# CH32V103C-R1.net
KiCad netlist of a schematic drawn in Altium Designer
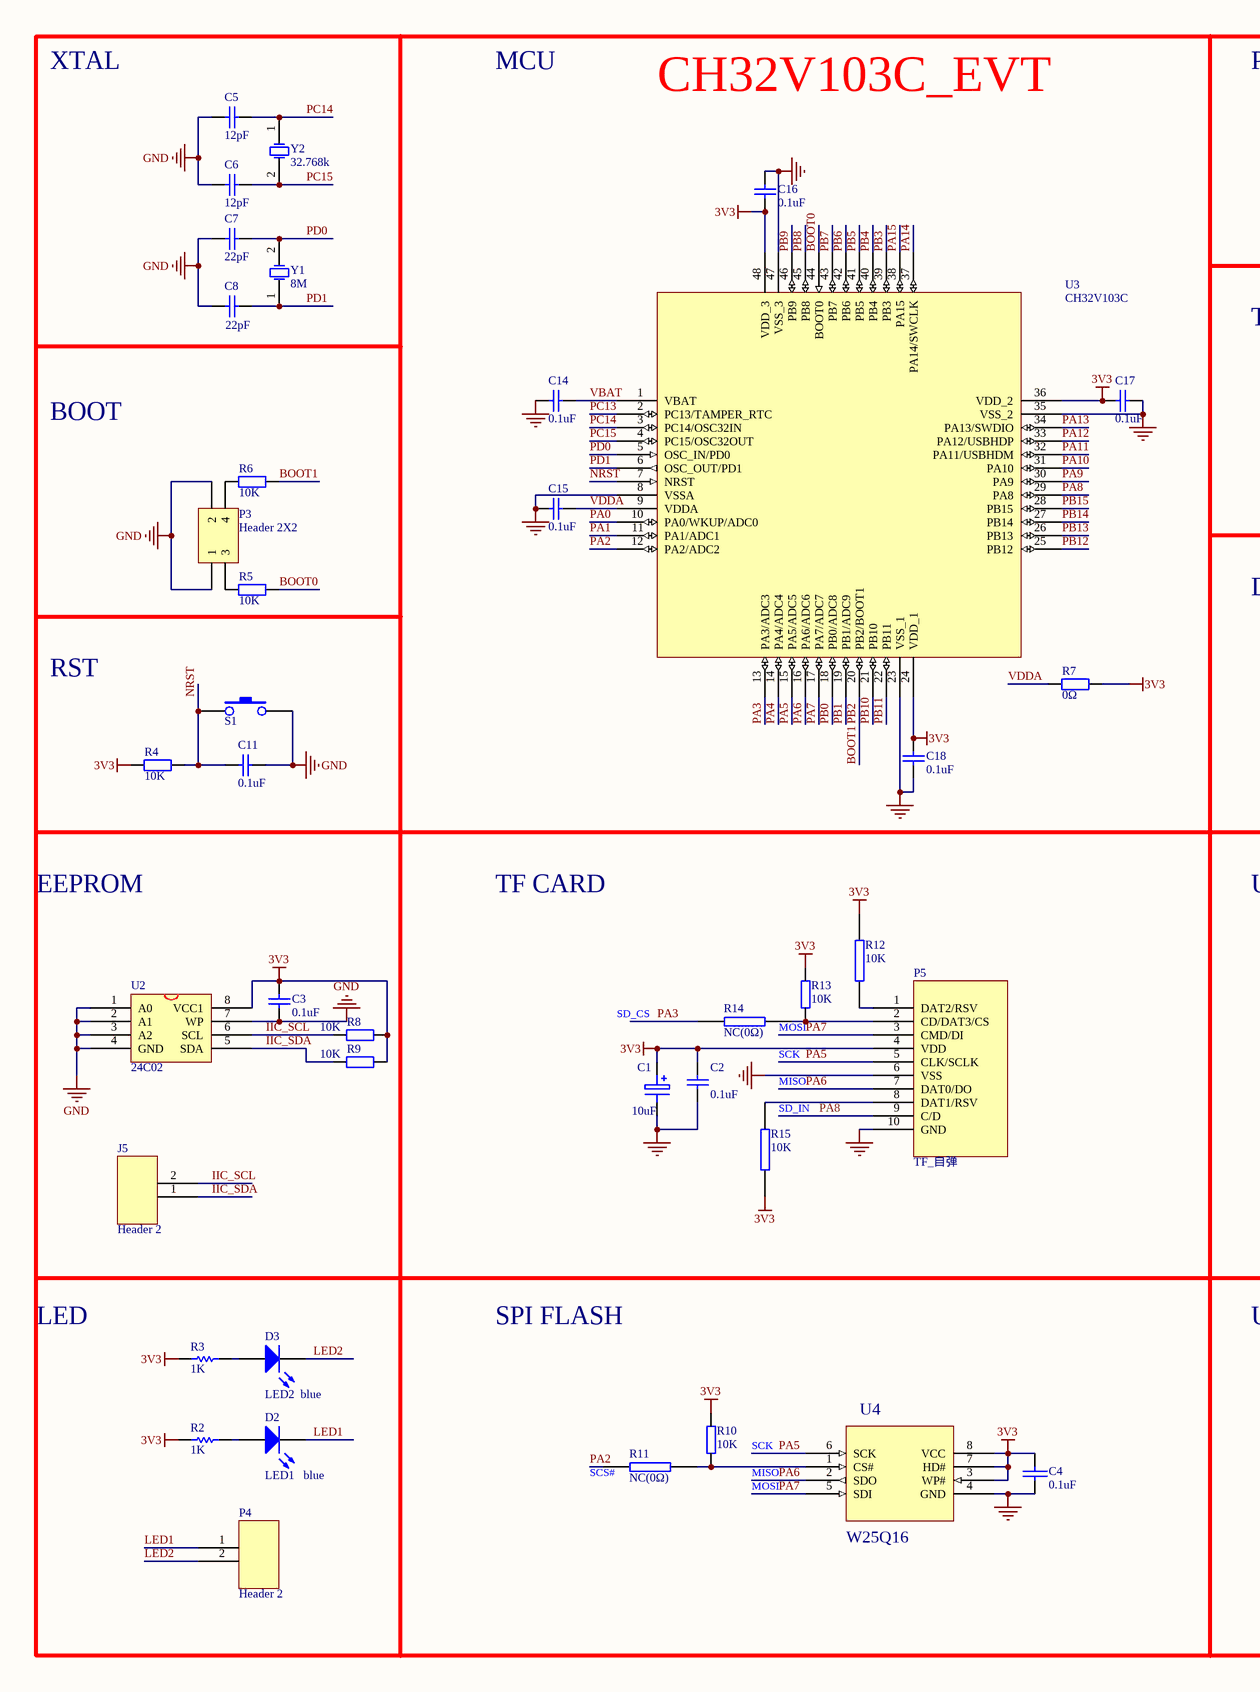
[diagram p0: CH32V103C-R1.SchDoc, left]
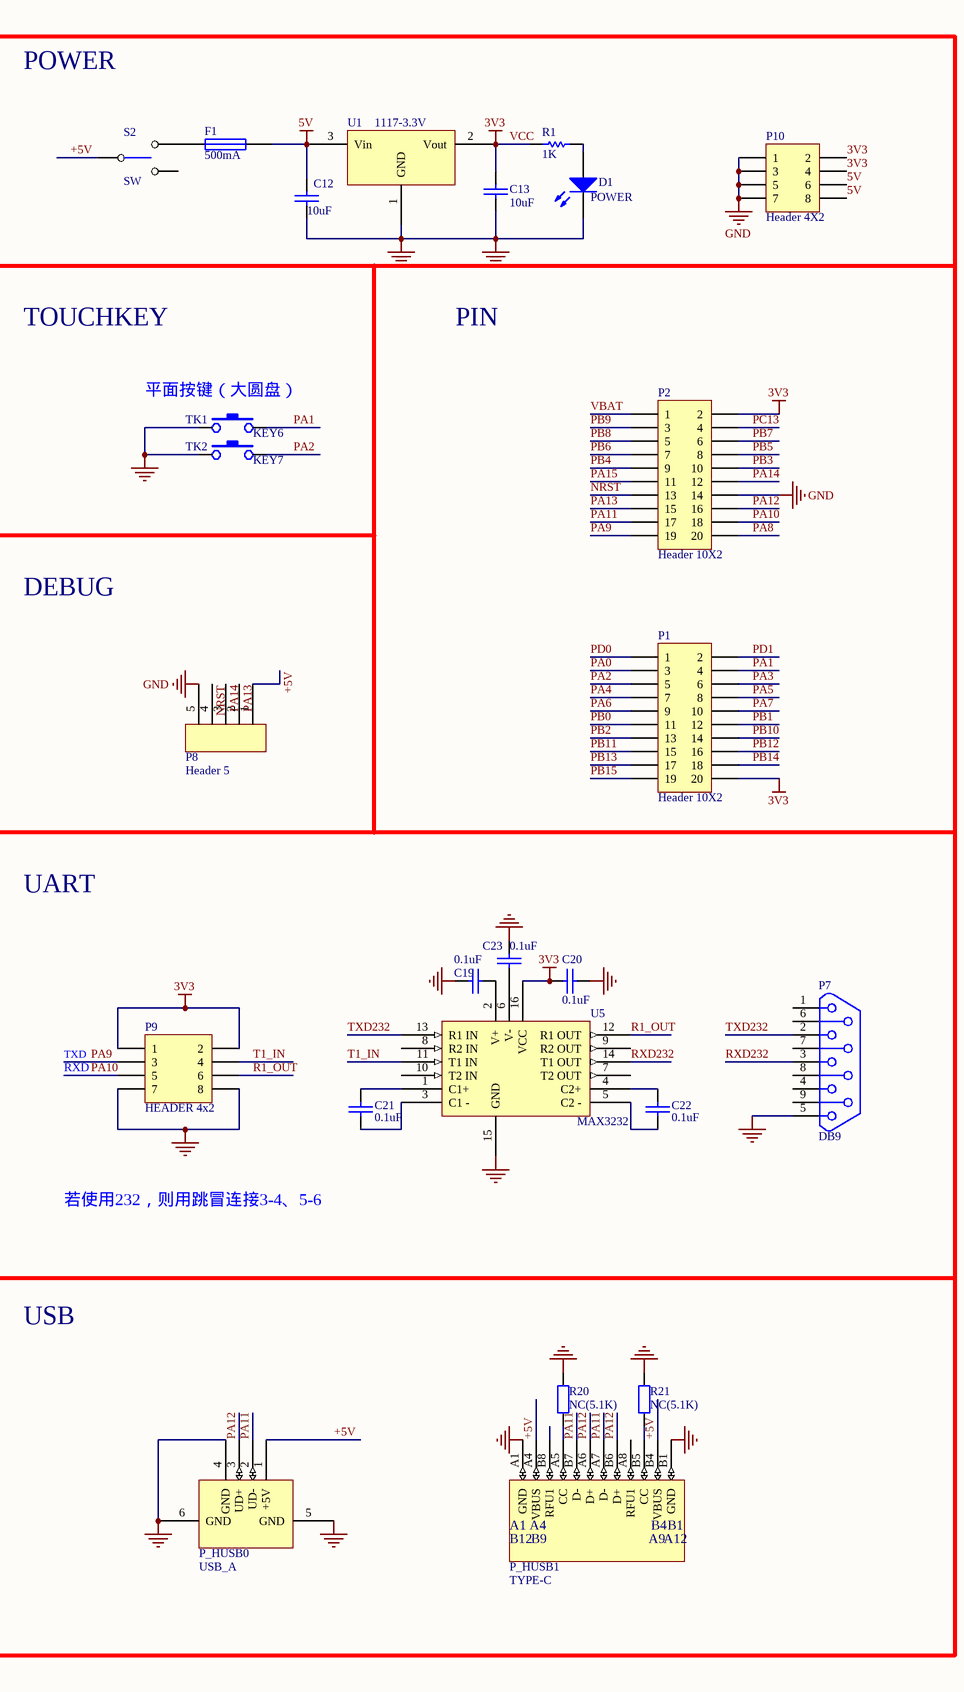
[diagram p1: CH32V103C-R1.SchDoc, right]

(export (version "E")
  (design (tool "Eeschema 10.0.6"))
  (components
    (comp (ref "C1")
      (value "10uF")
      (footprint "3216")
      (description "Electrolytic Capacitor")
      (libsource (lib "*") (part "ELECTRO1"))
    )
    (comp (ref "C2")
      (value "0.1uF")
      (footprint "0603")
      (description "Capacitor")
      (fields (field (name "PUBLISHER") "Altium Limited"))
      (libsource (lib "*") (part "Cap"))
    )
    (comp (ref "C3")
      (value "0.1uF")
      (footprint "0603")
      (description "Capacitor")
      (fields (field (name "PUBLISHER") "Altium Limited"))
      (libsource (lib "Miscellaneous Devices") (part "Cap"))
    )
    (comp (ref "C4")
      (value "0.1uF")
      (footprint "0603")
      (description "Capacitor")
      (libsource (lib "*") (part "CAP"))
    )
    (comp (ref "C5")
      (value "12pF")
      (footprint "0603")
      (description "Capacitor")
      (fields (field (name "PUBLISHER") "Altium Limited"))
      (libsource (lib "Miscellaneous Devices") (part "Cap"))
    )
    (comp (ref "C6")
      (value "12pF")
      (footprint "0603")
      (description "Capacitor")
      (fields (field (name "PUBLISHER") "Altium Limited"))
      (libsource (lib "Miscellaneous Devices") (part "Cap"))
    )
    (comp (ref "C7")
      (value "22pF")
      (footprint "0603")
      (description "Capacitor")
      (fields (field (name "PUBLISHER") "Altium Limited"))
      (libsource (lib "Miscellaneous Devices") (part "Cap"))
    )
    (comp (ref "C8")
      (value "22pF")
      (footprint "0603")
      (description "Capacitor")
      (fields (field (name "PUBLISHER") "Altium Limited"))
      (libsource (lib "Miscellaneous Devices") (part "Cap"))
    )
    (comp (ref "C11")
      (value "0.1uF")
      (footprint "0603")
      (description "Capacitor")
      (fields (field (name "PUBLISHER") "Altium Limited"))
      (libsource (lib "Miscellaneous Devices") (part "Cap"))
    )
    (comp (ref "C12")
      (value "10uF")
      (footprint "3216")
      (description "Capacitor")
      (libsource (lib "") (part "CAP_1"))
    )
    (comp (ref "C13")
      (value "10uF")
      (footprint "0603")
      (description "Capacitor")
      (libsource (lib "") (part "CAP_1"))
    )
    (comp (ref "C14")
      (value "0.1uF")
      (footprint "0603")
      (description "Capacitor")
      (fields (field (name "PUBLISHER") "Altium Limited"))
      (libsource (lib "*") (part "Cap"))
    )
    (comp (ref "C15")
      (value "0.1uF")
      (footprint "0603")
      (description "Capacitor")
      (fields (field (name "PUBLISHER") "Altium Limited"))
      (libsource (lib "*") (part "Cap"))
    )
    (comp (ref "C16")
      (value "0.1uF")
      (footprint "0603")
      (description "Capacitor")
      (fields (field (name "PUBLISHER") "Altium Limited"))
      (libsource (lib "*") (part "Cap"))
    )
    (comp (ref "C17")
      (value "0.1uF")
      (footprint "0603")
      (description "Capacitor")
      (fields (field (name "PUBLISHER") "Altium Limited"))
      (libsource (lib "*") (part "Cap"))
    )
    (comp (ref "C18")
      (value "0.1uF")
      (footprint "0603")
      (description "Capacitor")
      (fields (field (name "PUBLISHER") "Altium Limited"))
      (libsource (lib "*") (part "Cap"))
    )
    (comp (ref "C19")
      (value "0.1uF")
      (footprint "0603")
      (description "Capacitor")
      (libsource (lib "*") (part "CAP"))
    )
    (comp (ref "C20")
      (value "0.1uF")
      (footprint "0603")
      (description "Capacitor")
      (libsource (lib "*") (part "CAP"))
    )
    (comp (ref "C21")
      (value "0.1uF")
      (footprint "0603")
      (description "Capacitor")
      (libsource (lib "*") (part "CAP"))
    )
    (comp (ref "C22")
      (value "0.1uF")
      (footprint "0603")
      (description "Capacitor")
      (libsource (lib "*") (part "CAP"))
    )
    (comp (ref "C23")
      (value "0.1uF")
      (footprint "0603")
      (description "Capacitor")
      (libsource (lib "*") (part "CAP"))
    )
    (comp (ref "D1")
      (value "POWER")
      (footprint "0603+")
      (description "Typical INFRARED GaAs LED")
      (fields (field (name "PUBLISHER") "Altium Limited"))
      (libsource (lib "Miscellaneous Devices") (part "LED0"))
    )
    (comp (ref "D2")
      (value "LED1   blue")
      (footprint "0603+")
      (description "Typical INFRARED GaAs LED")
      (fields (field (name "PUBLISHER") "Altium Limited"))
      (libsource (lib "Miscellaneous Devices") (part "LED0"))
    )
    (comp (ref "D3")
      (value "LED2  blue")
      (footprint "0603+")
      (description "Typical INFRARED GaAs LED")
      (fields (field (name "PUBLISHER") "Altium Limited"))
      (libsource (lib "Miscellaneous Devices") (part "LED0"))
    )
    (comp (ref "F1")
      (value "500mA")
      (footprint "0603")
      (description "Fuse")
      (libsource (lib "*") (part "FUSE1"))
    )
    (comp (ref "J5") (value "Header 2") (footprint "SIP2-2.54mm") (libsource (lib "MYSCH") (part "2HEAD")))
    (comp (ref "P1")
      (value "Header 10X2")
      (footprint "IDC20-2.54mm")
      (description "Header, 10-Pin, Dual row")
      (fields (field (name "PUBLISHER") "Altium Limited"))
      (libsource (lib "Miscellaneous Connectors") (part "Header 10X2"))
    )
    (comp (ref "P2")
      (value "Header 10X2")
      (footprint "IDC20-2.54mm")
      (description "Header, 10-Pin, Dual row")
      (fields (field (name "PUBLISHER") "Altium Limited"))
      (libsource (lib "Miscellaneous Connectors") (part "Header 10X2"))
    )
    (comp (ref "P3")
      (value "Header 2X2")
      (footprint "HDR2X2")
      (description "Header, 2-Pin, Dual row")
      (fields (field (name "PUBLISHER") "Altium Limited"))
      (libsource (lib "Miscellaneous Connectors") (part "Header 2X2"))
    )
    (comp (ref "P4") (value "Header 2") (footprint "SIP2-2.54mm") (libsource (lib "") (part "2HEAD_1")))
    (comp (ref "P5") (value "TF_自弹") (footprint "TF") (libsource (lib "*") (part "TF_自弹")))
    (comp (ref "P7") (value "DB9") (footprint "DB9/M") (libsource (lib "*") (part "DB9")))
    (comp (ref "P8")
      (value "Header 5")
      (footprint "SIP5-2.54mm")
      (libsource (lib "PCB_Project1") (part "2HEAD"))
    )
    (comp (ref "P9")
      (value "HEADER 4x2")
      (footprint "MYPCB:IDC8-2.54mm")
      (description "Header, 4-Pin, Dual row")
      (libsource (lib "wch_sch_others") (part "HEADER 4x2"))
    )
    (comp (ref "P10")
      (value "Header 4X2")
      (footprint "IDC8-2.54mm")
      (description "Header, 4-Pin, Dual row")
      (fields (field (name "PUBLISHER") "Altium Limited"))
      (libsource (lib "Miscellaneous Connectors") (part "Header 4X2"))
    )
    (comp (ref "P_HUSB0")
      (value "USB_A")
      (footprint "USBA-l")
      (description "USB Port")
      (libsource (lib "CHXXXSCH") (part "USB"))
    )
    (comp (ref "P_HUSB1")
      (value "TYPE-C")
      (footprint "TYPE-C-Receptacle-2.0")
      (libsource (lib "*") (part "TYPE-C1"))
    )
    (comp (ref "R1")
      (value "1K")
      (footprint "0603")
      (description "Semiconductor Resistor")
      (fields (field (name "PUBLISHER") "Altium Limited"))
      (libsource (lib "Miscellaneous Devices") (part "Res Semi"))
    )
    (comp (ref "R2")
      (value "1K")
      (footprint "0603")
      (description "Semiconductor Resistor")
      (fields (field (name "PUBLISHER") "Altium Limited"))
      (libsource (lib "Miscellaneous Devices") (part "Res Semi"))
    )
    (comp (ref "R3")
      (value "1K")
      (footprint "0603")
      (description "Semiconductor Resistor")
      (fields (field (name "PUBLISHER") "Altium Limited"))
      (libsource (lib "Miscellaneous Devices") (part "Res Semi"))
    )
    (comp (ref "R4")
      (value "10K")
      (footprint "0603")
      (description "Resistor")
      (fields (field (name "PUBLISHER") "Altium Limited"))
      (libsource (lib "Miscellaneous Devices") (part "Res2"))
    )
    (comp (ref "R5")
      (value "10K")
      (footprint "0603")
      (description "Resistor")
      (fields (field (name "PUBLISHER") "Altium Limited"))
      (libsource (lib "Miscellaneous Devices") (part "Res2"))
    )
    (comp (ref "R6")
      (value "10K")
      (footprint "0603")
      (description "Resistor")
      (fields (field (name "PUBLISHER") "Altium Limited"))
      (libsource (lib "Miscellaneous Devices") (part "Res2"))
    )
    (comp (ref "R7")
      (value "0Ω")
      (footprint "0603")
      (description "Resistor")
      (fields (field (name "PUBLISHER") "Altium Limited"))
      (libsource (lib "Miscellaneous Devices") (part "Res2"))
    )
    (comp (ref "R8")
      (value "10K")
      (footprint "0603")
      (description "Resistor")
      (fields (field (name "PUBLISHER") "Altium Limited"))
      (libsource (lib "Miscellaneous Devices") (part "Res2"))
    )
    (comp (ref "R9")
      (value "10K")
      (footprint "0603")
      (description "Resistor")
      (fields (field (name "PUBLISHER") "Altium Limited"))
      (libsource (lib "Miscellaneous Devices") (part "Res2"))
    )
    (comp (ref "R10") (value "10K") (footprint "0603") (libsource (lib "*") (part "DZ")))
    (comp (ref "R11") (value "NC(0Ω)") (footprint "0603") (libsource (lib "*") (part "RES2")))
    (comp (ref "R12") (value "10K") (footprint "0603") (libsource (lib "*") (part "RES2")))
    (comp (ref "R13") (value "10K") (footprint "0603") (libsource (lib "*") (part "DZ")))
    (comp (ref "R14") (value "NC(0Ω)") (footprint "0603") (libsource (lib "*") (part "RES2")))
    (comp (ref "R15") (value "10K") (footprint "0603") (libsource (lib "*") (part "RES2")))
    (comp (ref "R20")
      (value "NC(5.1K)")
      (footprint "0603")
      (description "Resistor")
      (libsource (lib "") (part "Res2_1"))
    )
    (comp (ref "R21")
      (value "NC(5.1K)")
      (footprint "0603")
      (description "Resistor")
      (libsource (lib "") (part "Res2_1"))
    )
    (comp (ref "S1") (value "KEY") (footprint "贴片按键") (libsource (lib "CCDXPLIB") (part "KEY")))
    (comp (ref "S2") (value "SW") (footprint "KEY2") (libsource (lib "MYSCH") (part "SW")))
    (comp (ref "TK1") (value "KEY6") (footprint "TOUCHKEY-12mm") (libsource (lib "*") (part "KEY")))
    (comp (ref "TK2") (value "KEY7") (footprint "TOUCHKEY-12mm") (libsource (lib "*") (part "KEY")))
    (comp (ref "U1")
      (value "1117-3.3V")
      (footprint "SOT-223")
      (libsource (lib "wch_sch_others") (part "1117-3.3V"))
    )
    (comp (ref "U2") (value "24C02") (footprint "SOP8") (libsource (lib "Elite_SCH") (part "24C256")))
    (comp (ref "U3")
      (value "CH32V103C")
      (footprint "LQFP48")
      (description "RISC-V MCU with USB device & USB host & ADC & Touch Key")
      (libsource (lib "CHXXX") (part "CH32V103C"))
    )
    (comp (ref "U4")
      (value "W25Q16")
      (footprint "SOIC-8_208mil")
      (libsource (lib "*") (part "Pro89C.tmp_25F512_2"))
    )
    (comp (ref "U5")
      (value "MAX3232")
      (footprint "SOIC-16_150mil")
      (description "+-15KV ESD-PROTECTED, +5V RS-232 TRANSCEIVERS")
      (libsource (lib "*") (part "MAX232CPE(16)"))
    )
    (comp (ref "Y1")
      (value "8M")
      (footprint "XT62/28")
      (description "Crystal Oscillator")
      (fields (field (name "PUBLISHER") "Altium Limited"))
      (libsource (lib "Miscellaneous Devices") (part "XTAL"))
    )
    (comp (ref "Y2")
      (value "32.768k")
      (footprint "FC-135")
      (description "Crystal Oscillator")
      (fields (field (name "PUBLISHER") "Altium Limited"))
      (libsource (lib "Miscellaneous Devices") (part "XTAL"))
    )
  )
  (nets
    (net (code "1") (name "/+5V") (class "Default")
      (node (ref "P8") (pin "1") (pintype "passive"))
      (node (ref "P_HUSB0") (pin "1") (pinfunction "+5V_1") (pintype "power_in"))
      (node (ref "P_HUSB1") (pin "A4") (pinfunction "VBUS_A4") (pintype "bidirectional"))
      (node (ref "P_HUSB1") (pin "B4") (pinfunction "VBUS_B4") (pintype "bidirectional"))
      (node (ref "S2") (pin "1") (pinfunction "1_1") (pintype "passive"))
    )
    (net (code "3") (name "/BOOT0") (class "Default")
      (node (ref "R5") (pin "1") (pinfunction "1_1") (pintype "passive"))
      (node (ref "U3") (pin "44") (pinfunction "BOOT0_44") (pintype "input"))
    )
    (net (code "4") (name "/BOOT1") (class "Default")
      (node (ref "P1") (pin "13") (pinfunction "13_13") (pintype "passive"))
      (node (ref "R6") (pin "1") (pinfunction "1_1") (pintype "passive"))
      (node (ref "U3") (pin "20") (pinfunction "PB2/BOOT1_20") (pintype "bidirectional"))
    )
    (net (code "5") (name "/IIC_SCL") (class "Default")
      (node (ref "J5") (pin "2") (pintype "passive"))
      (node (ref "R8") (pin "2") (pinfunction "2_2") (pintype "passive"))
      (node (ref "U2") (pin "6") (pinfunction "SCL_6") (pintype "passive"))
    )
    (net (code "6") (name "/IIC_SDA") (class "Default")
      (node (ref "J5") (pin "1") (pintype "passive"))
      (node (ref "R9") (pin "2") (pinfunction "2_2") (pintype "passive"))
      (node (ref "U2") (pin "5") (pinfunction "SDA_5") (pintype "passive"))
    )
    (net (code "7") (name "/LED1") (class "Default")
      (node (ref "D2") (pin "2") (pinfunction "K_2") (pintype "passive"))
      (node (ref "P4") (pin "1") (pintype "passive"))
    )
    (net (code "8") (name "/LED2") (class "Default")
      (node (ref "D3") (pin "2") (pinfunction "K_2") (pintype "passive"))
      (node (ref "P4") (pin "2") (pintype "passive"))
    )
    (net (code "9") (name "/NRST") (class "Default")
      (node (ref "C11") (pin "2") (pinfunction "2_2") (pintype "passive"))
      (node (ref "P2") (pin "13") (pinfunction "13_13") (pintype "passive"))
      (node (ref "P8") (pin "4") (pintype "passive"))
      (node (ref "R4") (pin "1") (pinfunction "1_1") (pintype "passive"))
      (node (ref "S1") (pin "1") (pinfunction "1_1") (pintype "passive"))
      (node (ref "U3") (pin "7") (pinfunction "NRST_7") (pintype "input"))
    )
    (net (code "10") (name "/PA0") (class "Default")
      (node (ref "P1") (pin "3") (pinfunction "3_3") (pintype "passive"))
      (node (ref "U3") (pin "10") (pinfunction "PA0/WKUP/ADC0_10") (pintype "bidirectional"))
    )
    (net (code "11") (name "/PA1") (class "Default")
      (node (ref "P1") (pin "4") (pinfunction "4_4") (pintype "passive"))
      (node (ref "TK1") (pin "1") (pintype "passive"))
      (node (ref "U3") (pin "11") (pinfunction "PA1/ADC1_11") (pintype "bidirectional"))
    )
    (net (code "12") (name "/PA2") (class "Default")
      (node (ref "P1") (pin "5") (pinfunction "5_5") (pintype "passive"))
      (node (ref "R11") (pin "2") (pinfunction "2_2") (pintype "passive"))
      (node (ref "TK2") (pin "1") (pintype "passive"))
      (node (ref "U3") (pin "12") (pinfunction "PA2/ADC2_12") (pintype "bidirectional"))
    )
    (net (code "13") (name "/PA3") (class "Default")
      (node (ref "P1") (pin "6") (pinfunction "6_6") (pintype "passive"))
      (node (ref "R14") (pin "2") (pinfunction "2_2") (pintype "passive"))
      (node (ref "U3") (pin "13") (pinfunction "PA3/ADC3_13") (pintype "bidirectional"))
    )
    (net (code "14") (name "/PA4") (class "Default")
      (node (ref "P1") (pin "7") (pinfunction "7_7") (pintype "passive"))
      (node (ref "U3") (pin "14") (pinfunction "PA4/ADC4_14") (pintype "bidirectional"))
    )
    (net (code "15") (name "/PA5") (class "Default")
      (node (ref "P1") (pin "8") (pinfunction "8_8") (pintype "passive"))
      (node (ref "P5") (pin "5") (pinfunction "CLK/SCLK_5") (pintype "passive"))
      (node (ref "U3") (pin "15") (pinfunction "PA5/ADC5_15") (pintype "bidirectional"))
      (node (ref "U4") (pin "6") (pinfunction "SCK_6") (pintype "input"))
    )
    (net (code "16") (name "/PA6") (class "Default")
      (node (ref "P1") (pin "9") (pinfunction "9_9") (pintype "passive"))
      (node (ref "P5") (pin "7") (pinfunction "DAT0/DO_7") (pintype "passive"))
      (node (ref "U3") (pin "16") (pinfunction "PA6/ADC6_16") (pintype "bidirectional"))
      (node (ref "U4") (pin "2") (pinfunction "SDO_2") (pintype "output"))
    )
    (net (code "17") (name "/PA7") (class "Default")
      (node (ref "P1") (pin "10") (pinfunction "10_10") (pintype "passive"))
      (node (ref "P5") (pin "3") (pinfunction "CMD/DI_3") (pintype "passive"))
      (node (ref "U3") (pin "17") (pinfunction "PA7/ADC7_17") (pintype "bidirectional"))
      (node (ref "U4") (pin "5") (pinfunction "SDI_5") (pintype "input"))
    )
    (net (code "18") (name "/PA8") (class "Default")
      (node (ref "P2") (pin "20") (pinfunction "20_20") (pintype "passive"))
      (node (ref "P5") (pin "9") (pinfunction "C/D_9") (pintype "passive"))
      (node (ref "U3") (pin "29") (pinfunction "PA8_29") (pintype "bidirectional"))
    )
    (net (code "19") (name "/PA9") (class "Default")
      (node (ref "P2") (pin "19") (pinfunction "19_19") (pintype "passive"))
      (node (ref "P9") (pin "3") (pinfunction "3_3") (pintype "passive"))
      (node (ref "U3") (pin "30") (pinfunction "PA9_30") (pintype "bidirectional"))
    )
    (net (code "20") (name "/PA10") (class "Default")
      (node (ref "P2") (pin "18") (pinfunction "18_18") (pintype "passive"))
      (node (ref "P9") (pin "5") (pinfunction "5_5") (pintype "passive"))
      (node (ref "U3") (pin "31") (pinfunction "PA10_31") (pintype "bidirectional"))
    )
    (net (code "21") (name "/PA11") (class "Default")
      (node (ref "P2") (pin "17") (pinfunction "17_17") (pintype "passive"))
      (node (ref "P_HUSB0") (pin "2") (pinfunction "UD-_2") (pintype "bidirectional"))
      (node (ref "P_HUSB1") (pin "A7") (pinfunction "D-_A7") (pintype "bidirectional"))
      (node (ref "P_HUSB1") (pin "B7") (pinfunction "D-_B7") (pintype "bidirectional"))
      (node (ref "U3") (pin "32") (pinfunction "PA11/USBHDM_32") (pintype "bidirectional"))
    )
    (net (code "22") (name "/PA12") (class "Default")
      (node (ref "P2") (pin "16") (pinfunction "16_16") (pintype "passive"))
      (node (ref "P_HUSB0") (pin "3") (pinfunction "UD+_3") (pintype "bidirectional"))
      (node (ref "P_HUSB1") (pin "A6") (pinfunction "D+_A6") (pintype "bidirectional"))
      (node (ref "P_HUSB1") (pin "B6") (pinfunction "D+_B6") (pintype "bidirectional"))
      (node (ref "U3") (pin "33") (pinfunction "PA12/USBHDP_33") (pintype "bidirectional"))
    )
    (net (code "23") (name "/PA13") (class "Default")
      (node (ref "P2") (pin "15") (pinfunction "15_15") (pintype "passive"))
      (node (ref "P8") (pin "2") (pintype "passive"))
      (node (ref "U3") (pin "34") (pinfunction "PA13/SWDIO_34") (pintype "bidirectional"))
    )
    (net (code "24") (name "/PA14") (class "Default")
      (node (ref "P2") (pin "12") (pinfunction "12_12") (pintype "passive"))
      (node (ref "P8") (pin "3") (pintype "passive"))
      (node (ref "U3") (pin "37") (pinfunction "PA14/SWCLK_37") (pintype "bidirectional"))
    )
    (net (code "25") (name "/PA15") (class "Default")
      (node (ref "P2") (pin "11") (pinfunction "11_11") (pintype "passive"))
      (node (ref "U3") (pin "38") (pinfunction "PA15_38") (pintype "bidirectional"))
    )
    (net (code "26") (name "/PB0") (class "Default")
      (node (ref "P1") (pin "11") (pinfunction "11_11") (pintype "passive"))
      (node (ref "U3") (pin "18") (pinfunction "PB0/ADC8_18") (pintype "bidirectional"))
    )
    (net (code "27") (name "/PB1") (class "Default")
      (node (ref "P1") (pin "12") (pinfunction "12_12") (pintype "passive"))
      (node (ref "U3") (pin "19") (pinfunction "PB1/ADC9_19") (pintype "bidirectional"))
    )
    (net (code "28") (name "/PB3") (class "Default")
      (node (ref "P2") (pin "10") (pinfunction "10_10") (pintype "passive"))
      (node (ref "U3") (pin "39") (pinfunction "PB3_39") (pintype "bidirectional"))
    )
    (net (code "29") (name "/PB4") (class "Default")
      (node (ref "P2") (pin "9") (pinfunction "9_9") (pintype "passive"))
      (node (ref "U3") (pin "40") (pinfunction "PB4_40") (pintype "bidirectional"))
    )
    (net (code "30") (name "/PB5") (class "Default")
      (node (ref "P2") (pin "8") (pinfunction "8_8") (pintype "passive"))
      (node (ref "U3") (pin "41") (pinfunction "PB5_41") (pintype "bidirectional"))
    )
    (net (code "31") (name "/PB6") (class "Default")
      (node (ref "P2") (pin "7") (pinfunction "7_7") (pintype "passive"))
      (node (ref "U3") (pin "42") (pinfunction "PB6_42") (pintype "bidirectional"))
    )
    (net (code "32") (name "/PB7") (class "Default")
      (node (ref "P2") (pin "6") (pinfunction "6_6") (pintype "passive"))
      (node (ref "U3") (pin "43") (pinfunction "PB7_43") (pintype "bidirectional"))
    )
    (net (code "33") (name "/PB8") (class "Default")
      (node (ref "P2") (pin "5") (pinfunction "5_5") (pintype "passive"))
      (node (ref "U3") (pin "45") (pinfunction "PB8_45") (pintype "bidirectional"))
    )
    (net (code "34") (name "/PB9") (class "Default")
      (node (ref "P2") (pin "3") (pinfunction "3_3") (pintype "passive"))
      (node (ref "U3") (pin "46") (pinfunction "PB9_46") (pintype "bidirectional"))
    )
    (net (code "35") (name "/PB10") (class "Default")
      (node (ref "P1") (pin "14") (pinfunction "14_14") (pintype "passive"))
      (node (ref "U3") (pin "21") (pinfunction "PB10_21") (pintype "bidirectional"))
    )
    (net (code "36") (name "/PB11") (class "Default")
      (node (ref "P1") (pin "15") (pinfunction "15_15") (pintype "passive"))
      (node (ref "U3") (pin "22") (pinfunction "PB11_22") (pintype "bidirectional"))
    )
    (net (code "37") (name "/PB12") (class "Default")
      (node (ref "P1") (pin "16") (pinfunction "16_16") (pintype "passive"))
      (node (ref "U3") (pin "25") (pinfunction "PB12_25") (pintype "bidirectional"))
    )
    (net (code "38") (name "/PB13") (class "Default")
      (node (ref "P1") (pin "17") (pinfunction "17_17") (pintype "passive"))
      (node (ref "U3") (pin "26") (pinfunction "PB13_26") (pintype "bidirectional"))
    )
    (net (code "39") (name "/PB14") (class "Default")
      (node (ref "P1") (pin "18") (pinfunction "18_18") (pintype "passive"))
      (node (ref "U3") (pin "27") (pinfunction "PB14_27") (pintype "bidirectional"))
    )
    (net (code "40") (name "/PB15") (class "Default")
      (node (ref "P1") (pin "19") (pinfunction "19_19") (pintype "passive"))
      (node (ref "U3") (pin "28") (pinfunction "PB15_28") (pintype "bidirectional"))
    )
    (net (code "41") (name "/PC13") (class "Default")
      (node (ref "P2") (pin "4") (pinfunction "4_4") (pintype "passive"))
      (node (ref "U3") (pin "2") (pinfunction "PC13/TAMPER_RTC_2") (pintype "bidirectional"))
    )
    (net (code "42") (name "/PC14") (class "Default")
      (node (ref "C5") (pin "1") (pinfunction "1_1") (pintype "passive"))
      (node (ref "U3") (pin "3") (pinfunction "PC14/OSC32IN_3") (pintype "bidirectional"))
      (node (ref "Y2") (pin "1") (pinfunction "OSC1_1") (pintype "passive"))
    )
    (net (code "43") (name "/PC15") (class "Default")
      (node (ref "C6") (pin "1") (pinfunction "1_1") (pintype "passive"))
      (node (ref "U3") (pin "4") (pinfunction "PC15/OSC32OUT_4") (pintype "bidirectional"))
      (node (ref "Y2") (pin "2") (pinfunction "OSC2_2") (pintype "passive"))
    )
    (net (code "44") (name "/PD0") (class "Default")
      (node (ref "C7") (pin "2") (pinfunction "2_2") (pintype "passive"))
      (node (ref "P1") (pin "1") (pinfunction "1_1") (pintype "passive"))
      (node (ref "U3") (pin "5") (pinfunction "OSC_IN/PD0_5") (pintype "input"))
      (node (ref "Y1") (pin "2") (pinfunction "OSC2_2") (pintype "passive"))
    )
    (net (code "45") (name "/PD1") (class "Default")
      (node (ref "C8") (pin "2") (pinfunction "2_2") (pintype "passive"))
      (node (ref "P1") (pin "2") (pinfunction "2_2") (pintype "passive"))
      (node (ref "U3") (pin "6") (pinfunction "OSC_OUT/PD1_6") (pintype "output"))
      (node (ref "Y1") (pin "1") (pinfunction "OSC1_1") (pintype "passive"))
    )
    (net (code "46") (name "/R1_OUT") (class "Default")
      (node (ref "P9") (pin "6") (pinfunction "6_6") (pintype "passive"))
      (node (ref "U5") (pin "12") (pinfunction "R1_OUT_12") (pintype "output"))
    )
    (net (code "47") (name "/RXD232") (class "Default")
      (node (ref "P7") (pin "3") (pinfunction "3_3") (pintype "passive"))
      (node (ref "U5") (pin "14") (pinfunction "T1_OUT_14") (pintype "output"))
    )
    (net (code "48") (name "/T1_IN") (class "Default")
      (node (ref "P9") (pin "4") (pinfunction "4_4") (pintype "passive"))
      (node (ref "U5") (pin "11") (pinfunction "T1_IN_11") (pintype "input"))
    )
    (net (code "49") (name "/TXD232") (class "Default")
      (node (ref "P7") (pin "2") (pinfunction "2_2") (pintype "passive"))
      (node (ref "U5") (pin "13") (pinfunction "R1_IN_13") (pintype "input"))
    )
    (net (code "50") (name "/VBAT") (class "Default")
      (node (ref "C14") (pin "1") (pinfunction "1_1") (pintype "passive"))
      (node (ref "P2") (pin "1") (pinfunction "1_1") (pintype "passive"))
      (node (ref "U3") (pin "1") (pinfunction "VBAT_1") (pintype "power_in"))
    )
    (net (code "51") (name "/VDDA") (class "Default")
      (node (ref "C15") (pin "1") (pinfunction "1_1") (pintype "passive"))
      (node (ref "R7") (pin "2") (pinfunction "2_2") (pintype "passive"))
      (node (ref "U3") (pin "9") (pinfunction "VDDA_9") (pintype "passive"))
    )
    (net (code "52") (name "3V3") (class "Default")
      (node (ref "C1") (pin "1") (pinfunction "1_1") (pintype "passive"))
      (node (ref "C13") (pin "1") (pinfunction "1_1") (pintype "passive"))
      (node (ref "C16") (pin "2") (pinfunction "2_2") (pintype "passive"))
      (node (ref "C17") (pin "2") (pinfunction "2_2") (pintype "passive"))
      (node (ref "C18") (pin "2") (pinfunction "2_2") (pintype "passive"))
      (node (ref "C2") (pin "1") (pinfunction "1_1") (pintype "passive"))
      (node (ref "C20") (pin "2") (pinfunction "2_2") (pintype "passive"))
      (node (ref "C3") (pin "2") (pinfunction "2_2") (pintype "passive"))
      (node (ref "C4") (pin "2") (pinfunction "2_2") (pintype "passive"))
      (node (ref "P1") (pin "20") (pinfunction "20_20") (pintype "passive"))
      (node (ref "P10") (pin "2") (pinfunction "2_2") (pintype "passive"))
      (node (ref "P10") (pin "4") (pinfunction "4_4") (pintype "passive"))
      (node (ref "P2") (pin "2") (pinfunction "2_2") (pintype "passive"))
      (node (ref "P5") (pin "4") (pinfunction "VDD_4") (pintype "passive"))
      (node (ref "P9") (pin "1") (pinfunction "1_1") (pintype "passive"))
      (node (ref "P9") (pin "2") (pinfunction "2_2") (pintype "passive"))
      (node (ref "R1") (pin "2") (pinfunction "2_2") (pintype "passive"))
      (node (ref "R10") (pin "2") (pintype "passive"))
      (node (ref "R12") (pin "2") (pinfunction "2_2") (pintype "passive"))
      (node (ref "R13") (pin "2") (pintype "passive"))
      (node (ref "R15") (pin "1") (pinfunction "1_1") (pintype "passive"))
      (node (ref "R2") (pin "1") (pinfunction "1_1") (pintype "passive"))
      (node (ref "R3") (pin "1") (pinfunction "1_1") (pintype "passive"))
      (node (ref "R4") (pin "2") (pinfunction "2_2") (pintype "passive"))
      (node (ref "R7") (pin "1") (pinfunction "1_1") (pintype "passive"))
      (node (ref "R8") (pin "1") (pinfunction "1_1") (pintype "passive"))
      (node (ref "R9") (pin "1") (pinfunction "1_1") (pintype "passive"))
      (node (ref "U1") (pin "2") (pinfunction "Vout_2") (pintype "passive"))
      (node (ref "U2") (pin "8") (pinfunction "VCC1_8") (pintype "passive"))
      (node (ref "U3") (pin "24") (pinfunction "VDD_1_24") (pintype "passive"))
      (node (ref "U3") (pin "36") (pinfunction "VDD_2_36") (pintype "passive"))
      (node (ref "U3") (pin "48") (pinfunction "VDD_3_48") (pintype "passive"))
      (node (ref "U4") (pin "3") (pinfunction "WP#_3") (pintype "input"))
      (node (ref "U4") (pin "7") (pinfunction "HD#_7") (pintype "power_in"))
      (node (ref "U4") (pin "8") (pinfunction "VCC_8") (pintype "power_in"))
      (node (ref "U5") (pin "16") (pinfunction "VCC_16") (pintype "power_in"))
    )
    (net (code "53") (name "5V") (class "Default")
      (node (ref "C12") (pin "1") (pinfunction "1_1") (pintype "passive"))
      (node (ref "F1") (pin "2") (pinfunction "2_2") (pintype "passive"))
      (node (ref "P10") (pin "6") (pinfunction "6_6") (pintype "passive"))
      (node (ref "P10") (pin "8") (pinfunction "8_8") (pintype "passive"))
      (node (ref "U1") (pin "3") (pinfunction "Vin_3") (pintype "passive"))
    )
    (net (code "54") (name "GND") (class "Default")
      (node (ref "C1") (pin "2") (pinfunction "2_2") (pintype "passive"))
      (node (ref "C11") (pin "1") (pinfunction "1_1") (pintype "passive"))
      (node (ref "C12") (pin "2") (pinfunction "2_2") (pintype "passive"))
      (node (ref "C13") (pin "2") (pinfunction "2_2") (pintype "passive"))
      (node (ref "C14") (pin "2") (pinfunction "2_2") (pintype "passive"))
      (node (ref "C15") (pin "2") (pinfunction "2_2") (pintype "passive"))
      (node (ref "C16") (pin "1") (pinfunction "1_1") (pintype "passive"))
      (node (ref "C17") (pin "1") (pinfunction "1_1") (pintype "passive"))
      (node (ref "C18") (pin "1") (pinfunction "1_1") (pintype "passive"))
      (node (ref "C19") (pin "2") (pinfunction "2_2") (pintype "passive"))
      (node (ref "C2") (pin "2") (pinfunction "2_2") (pintype "passive"))
      (node (ref "C20") (pin "1") (pinfunction "1_1") (pintype "passive"))
      (node (ref "C23") (pin "2") (pinfunction "2_2") (pintype "passive"))
      (node (ref "C3") (pin "1") (pinfunction "1_1") (pintype "passive"))
      (node (ref "C4") (pin "1") (pinfunction "1_1") (pintype "passive"))
      (node (ref "C5") (pin "2") (pinfunction "2_2") (pintype "passive"))
      (node (ref "C6") (pin "2") (pinfunction "2_2") (pintype "passive"))
      (node (ref "C7") (pin "1") (pinfunction "1_1") (pintype "passive"))
      (node (ref "C8") (pin "1") (pinfunction "1_1") (pintype "passive"))
      (node (ref "D1") (pin "2") (pinfunction "K_2") (pintype "passive"))
      (node (ref "P10") (pin "1") (pinfunction "1_1") (pintype "passive"))
      (node (ref "P10") (pin "3") (pinfunction "3_3") (pintype "passive"))
      (node (ref "P10") (pin "5") (pinfunction "5_5") (pintype "passive"))
      (node (ref "P10") (pin "7") (pinfunction "7_7") (pintype "passive"))
      (node (ref "P2") (pin "14") (pinfunction "14_14") (pintype "passive"))
      (node (ref "P3") (pin "1") (pinfunction "1_1") (pintype "passive"))
      (node (ref "P3") (pin "2") (pinfunction "2_2") (pintype "passive"))
      (node (ref "P5") (pin "10") (pinfunction "GND_10") (pintype "passive"))
      (node (ref "P5") (pin "6") (pinfunction "VSS_6") (pintype "passive"))
      (node (ref "P7") (pin "5") (pinfunction "5_5") (pintype "passive"))
      (node (ref "P8") (pin "5") (pintype "passive"))
      (node (ref "P9") (pin "7") (pinfunction "7_7") (pintype "passive"))
      (node (ref "P9") (pin "8") (pinfunction "8_8") (pintype "passive"))
      (node (ref "P_HUSB0") (pin "4") (pinfunction "GND_4") (pintype "power_in"))
      (node (ref "P_HUSB0") (pin "5") (pinfunction "GND_5") (pintype "power_in"))
      (node (ref "P_HUSB0") (pin "6") (pinfunction "GND_6") (pintype "power_in"))
      (node (ref "P_HUSB1") (pin "A1") (pinfunction "GND_A1") (pintype "bidirectional"))
      (node (ref "P_HUSB1") (pin "B1") (pinfunction "GND_B1") (pintype "bidirectional"))
      (node (ref "R20") (pin "2") (pinfunction "2_2") (pintype "passive"))
      (node (ref "R21") (pin "2") (pinfunction "2_2") (pintype "passive"))
      (node (ref "S1") (pin "3") (pinfunction "3_3") (pintype "passive"))
      (node (ref "TK1") (pin "3") (pintype "passive"))
      (node (ref "TK2") (pin "3") (pintype "passive"))
      (node (ref "U1") (pin "1") (pinfunction "GND_1") (pintype "passive"))
      (node (ref "U2") (pin "1") (pinfunction "A0_1") (pintype "passive"))
      (node (ref "U2") (pin "2") (pinfunction "A1_2") (pintype "passive"))
      (node (ref "U2") (pin "3") (pinfunction "A2_3") (pintype "passive"))
      (node (ref "U2") (pin "4") (pinfunction "GND_4") (pintype "passive"))
      (node (ref "U2") (pin "7") (pinfunction "WP_7") (pintype "passive"))
      (node (ref "U3") (pin "23") (pinfunction "VSS_1_23") (pintype "passive"))
      (node (ref "U3") (pin "35") (pinfunction "VSS_2_35") (pintype "passive"))
      (node (ref "U3") (pin "47") (pinfunction "VSS_3_47") (pintype "passive"))
      (node (ref "U3") (pin "8") (pinfunction "VSSA_8") (pintype "passive"))
      (node (ref "U4") (pin "4") (pinfunction "GND_4") (pintype "power_in"))
      (node (ref "U5") (pin "15") (pinfunction "GND_15") (pintype "power_in"))
    )
    (net (code "55") (name "Net-(D1-A)") (class "Default")
      (node (ref "D1") (pin "1") (pinfunction "A_1") (pintype "passive"))
      (node (ref "R1") (pin "1") (pinfunction "1_1") (pintype "passive"))
    )
    (net (code "56") (name "Net-(D2-A)") (class "Default")
      (node (ref "D2") (pin "1") (pinfunction "A_1") (pintype "passive"))
      (node (ref "R2") (pin "2") (pinfunction "2_2") (pintype "passive"))
    )
    (net (code "57") (name "Net-(D3-A)") (class "Default")
      (node (ref "D3") (pin "1") (pinfunction "A_1") (pintype "passive"))
      (node (ref "R3") (pin "2") (pinfunction "2_2") (pintype "passive"))
    )
    (net (code "58") (name "Net-(F1-Pad1)") (class "Default")
      (node (ref "F1") (pin "1") (pinfunction "1_1") (pintype "passive"))
      (node (ref "S2") (pin "2") (pinfunction "2_2") (pintype "passive"))
    )
    (net (code "59") (name "Net-(P3-Pad3)") (class "Default")
      (node (ref "P3") (pin "3") (pinfunction "3_3") (pintype "passive"))
      (node (ref "R5") (pin "2") (pinfunction "2_2") (pintype "passive"))
    )
    (net (code "60") (name "Net-(P3-Pad4)") (class "Default")
      (node (ref "P3") (pin "4") (pinfunction "4_4") (pintype "passive"))
      (node (ref "R6") (pin "2") (pinfunction "2_2") (pintype "passive"))
    )
    (net (code "61") (name "Net-(P5-CD{slash}DAT3{slash}CS)") (class "Default")
      (node (ref "P5") (pin "2") (pinfunction "CD/DAT3/CS_2") (pintype "passive"))
      (node (ref "R13") (pin "1") (pintype "passive"))
      (node (ref "R14") (pin "1") (pinfunction "1_1") (pintype "passive"))
    )
    (net (code "62") (name "Net-(P5-DAT1{slash}RSV)") (class "Default")
      (node (ref "P5") (pin "8") (pinfunction "DAT1/RSV_8") (pintype "passive"))
      (node (ref "R15") (pin "2") (pinfunction "2_2") (pintype "passive"))
    )
    (net (code "63") (name "Net-(P5-DAT2{slash}RSV)") (class "Default")
      (node (ref "P5") (pin "1") (pinfunction "DAT2/RSV_1") (pintype "passive"))
      (node (ref "R12") (pin "1") (pinfunction "1_1") (pintype "passive"))
    )
    (net (code "64") (name "Net-(P_HUSB1-CC-PadA5)") (class "Default")
      (node (ref "P_HUSB1") (pin "A5") (pinfunction "CC_A5") (pintype "bidirectional"))
      (node (ref "R20") (pin "1") (pinfunction "1_1") (pintype "passive"))
    )
    (net (code "65") (name "Net-(P_HUSB1-CC-PadB5)") (class "Default")
      (node (ref "P_HUSB1") (pin "B5") (pinfunction "CC_B5") (pintype "bidirectional"))
      (node (ref "R21") (pin "1") (pinfunction "1_1") (pintype "passive"))
    )
    (net (code "66") (name "Net-(U4-CS#)") (class "Default")
      (node (ref "R10") (pin "1") (pintype "passive"))
      (node (ref "R11") (pin "1") (pinfunction "1_1") (pintype "passive"))
      (node (ref "U4") (pin "1") (pinfunction "CS#_1") (pintype "input"))
    )
    (net (code "67") (name "Net-(U5-C1+)") (class "Default")
      (node (ref "C21") (pin "1") (pinfunction "1_1") (pintype "passive"))
      (node (ref "U5") (pin "1") (pinfunction "C1+_1") (pintype "passive"))
    )
    (net (code "68") (name "Net-(U5-C1_-)") (class "Default")
      (node (ref "C21") (pin "2") (pinfunction "2_2") (pintype "passive"))
      (node (ref "U5") (pin "3") (pinfunction "C1_-_3") (pintype "passive"))
    )
    (net (code "69") (name "Net-(U5-C2+)") (class "Default")
      (node (ref "C22") (pin "1") (pinfunction "1_1") (pintype "passive"))
      (node (ref "U5") (pin "4") (pinfunction "C2+_4") (pintype "passive"))
    )
    (net (code "70") (name "Net-(U5-C2_-)") (class "Default")
      (node (ref "C22") (pin "2") (pinfunction "2_2") (pintype "passive"))
      (node (ref "U5") (pin "5") (pinfunction "C2_-_5") (pintype "passive"))
    )
    (net (code "71") (name "V+") (class "Default")
      (node (ref "C19") (pin "1") (pinfunction "1_1") (pintype "passive"))
      (node (ref "U5") (pin "2") (pinfunction "V+_2") (pintype "power_in"))
    )
    (net (code "72") (name "V-") (class "Default")
      (node (ref "C23") (pin "1") (pinfunction "1_1") (pintype "passive"))
      (node (ref "U5") (pin "6") (pinfunction "V-_6") (pintype "power_in"))
    )
    (net (code "73") (name "unconnected-(P7-Pad1)") (class "Default")
      (node (ref "P7") (pin "1") (pinfunction "1_1") (pintype "passive"))
    )
    (net (code "74") (name "unconnected-(P7-Pad4)") (class "Default")
      (node (ref "P7") (pin "4") (pinfunction "4_4") (pintype "passive"))
    )
    (net (code "75") (name "unconnected-(P7-Pad6)") (class "Default")
      (node (ref "P7") (pin "6") (pinfunction "6_6") (pintype "passive"))
    )
    (net (code "76") (name "unconnected-(P7-Pad7)") (class "Default")
      (node (ref "P7") (pin "7") (pinfunction "7_7") (pintype "passive"))
    )
    (net (code "77") (name "unconnected-(P7-Pad8)") (class "Default")
      (node (ref "P7") (pin "8") (pinfunction "8_8") (pintype "passive"))
    )
    (net (code "78") (name "unconnected-(P7-Pad9)") (class "Default")
      (node (ref "P7") (pin "9") (pinfunction "9_9") (pintype "passive"))
    )
    (net (code "79") (name "unconnected-(P_HUSB1-RFU1-PadA8)") (class "Default")
      (node (ref "P_HUSB1") (pin "A8") (pinfunction "RFU1_A8") (pintype "bidirectional"))
    )
    (net (code "80") (name "unconnected-(P_HUSB1-RFU1-PadB8)") (class "Default")
      (node (ref "P_HUSB1") (pin "B8") (pinfunction "RFU1_B8") (pintype "bidirectional"))
    )
    (net (code "81") (name "unconnected-(S2-Pad3)") (class "Default")
      (node (ref "S2") (pin "3") (pinfunction "3_3") (pintype "passive"))
    )
    (net (code "82") (name "unconnected-(U5-R2_IN-Pad8)") (class "Default")
      (node (ref "U5") (pin "8") (pinfunction "R2_IN_8") (pintype "input"))
    )
    (net (code "83") (name "unconnected-(U5-R2_OUT-Pad9)") (class "Default")
      (node (ref "U5") (pin "9") (pinfunction "R2_OUT_9") (pintype "output"))
    )
    (net (code "84") (name "unconnected-(U5-T2_IN-Pad10)") (class "Default")
      (node (ref "U5") (pin "10") (pinfunction "T2_IN_10") (pintype "input"))
    )
    (net (code "85") (name "unconnected-(U5-T2_OUT-Pad7)") (class "Default")
      (node (ref "U5") (pin "7") (pinfunction "T2_OUT_7") (pintype "output"))
    )
  )
)
